# SHEET1.net
KiCad netlist of a schematic drawn in Altium Designer
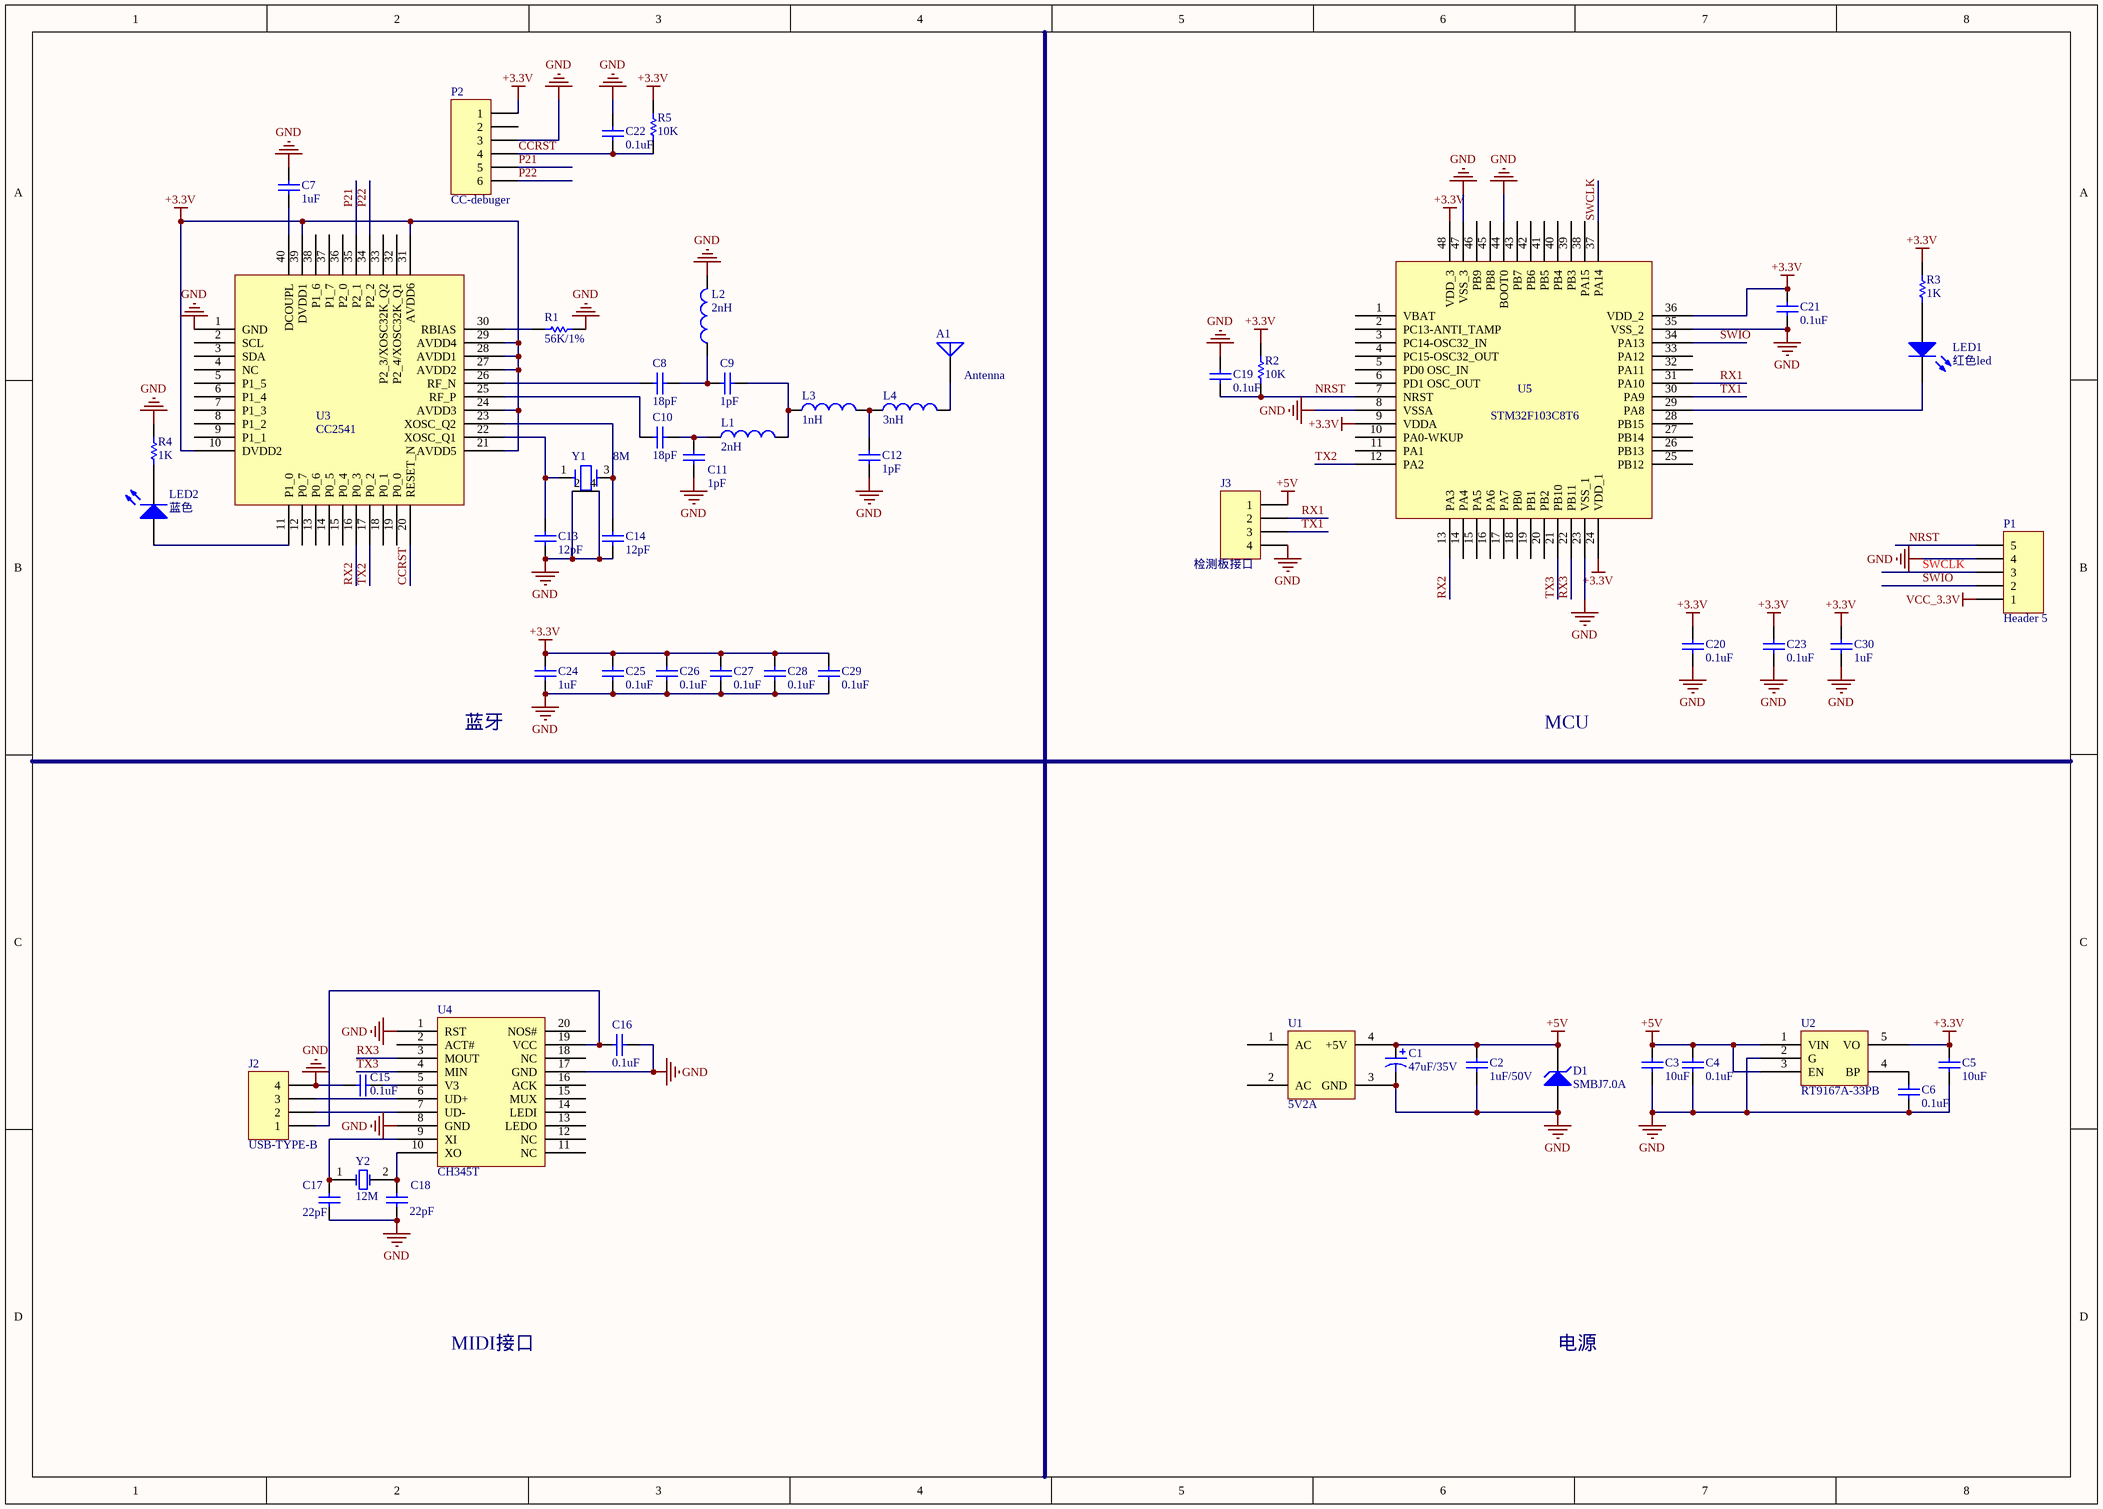
[diagram p0: SHEET1.SCHDOC]

(export (version "E")
  (design (tool "Eeschema 10.0.6"))
  (components
    (comp (ref "A1")
      (value "Antenna")
      (footprint "RF:ANT-PCB-2.4G-IFA-AN043-TI-ORIGIN")
      (description "Generic Antenna")
      (fields (field (name "PUBLISHER") "Altium Limited"))
      (libsource (lib "Miscellaneous Devices") (part "Antenna"))
    )
    (comp (ref "C1")
      (value "47uF/35V")
      (footprint "A")
      (description "Polarized Capacitor (Radial)")
      (fields (field (name "PUBLISHER") "Altium Limited"))
      (libsource (lib "Miscellaneous Devices") (part "Cap Pol1"))
    )
    (comp (ref "C2")
      (value "1uF/50V")
      (footprint "0805")
      (description "Capacitor")
      (fields (field (name "PUBLISHER") "Altium Limited"))
      (libsource (lib "Miscellaneous Devices") (part "Cap"))
    )
    (comp (ref "C3")
      (value "10uF")
      (footprint "0805")
      (description "Capacitor")
      (fields (field (name "PUBLISHER") "Altium Limited"))
      (libsource (lib "Miscellaneous Devices") (part "Cap"))
    )
    (comp (ref "C4")
      (value "0.1uF")
      (description "Capacitor")
      (fields (field (name "PUBLISHER") "Altium Limited"))
      (libsource (lib "Miscellaneous Devices") (part "Cap"))
    )
    (comp (ref "C5")
      (value "10uF")
      (footprint "0805")
      (description "Capacitor")
      (fields (field (name "PUBLISHER") "Altium Limited"))
      (libsource (lib "Miscellaneous Devices") (part "Cap"))
    )
    (comp (ref "C6")
      (value "0.1uF")
      (description "Capacitor")
      (fields (field (name "PUBLISHER") "Altium Limited"))
      (libsource (lib "Miscellaneous Devices") (part "Cap"))
    )
    (comp (ref "C7")
      (value "1uF")
      (description "Capacitor")
      (fields (field (name "PUBLISHER") "Altium Limited"))
      (libsource (lib "Miscellaneous Devices") (part "Cap"))
    )
    (comp (ref "C8")
      (value "18pF")
      (description "Capacitor")
      (fields (field (name "PUBLISHER") "Altium Limited"))
      (libsource (lib "Miscellaneous Devices") (part "Cap"))
    )
    (comp (ref "C9")
      (value "1pF")
      (description "Capacitor")
      (fields (field (name "PUBLISHER") "Altium Limited"))
      (libsource (lib "Miscellaneous Devices") (part "Cap"))
    )
    (comp (ref "C10")
      (value "18pF")
      (description "Capacitor")
      (fields (field (name "PUBLISHER") "Altium Limited"))
      (libsource (lib "Miscellaneous Devices") (part "Cap"))
    )
    (comp (ref "C11")
      (value "1pF")
      (description "Capacitor")
      (fields (field (name "PUBLISHER") "Altium Limited"))
      (libsource (lib "Miscellaneous Devices") (part "Cap"))
    )
    (comp (ref "C12")
      (value "1pF")
      (description "Capacitor")
      (fields (field (name "PUBLISHER") "Altium Limited"))
      (libsource (lib "Miscellaneous Devices") (part "Cap"))
    )
    (comp (ref "C13")
      (value "12pF")
      (description "Capacitor")
      (fields (field (name "PUBLISHER") "Altium Limited"))
      (libsource (lib "Miscellaneous Devices") (part "Cap"))
    )
    (comp (ref "C14")
      (value "12pF")
      (description "Capacitor")
      (fields (field (name "PUBLISHER") "Altium Limited"))
      (libsource (lib "Miscellaneous Devices") (part "Cap"))
    )
    (comp (ref "C15")
      (value "0.1uF")
      (description "Capacitor")
      (fields (field (name "PUBLISHER") "Altium Limited"))
      (libsource (lib "Miscellaneous Devices") (part "Cap"))
    )
    (comp (ref "C16")
      (value "0.1uF")
      (description "Capacitor")
      (fields (field (name "PUBLISHER") "Altium Limited"))
      (libsource (lib "Miscellaneous Devices") (part "Cap"))
    )
    (comp (ref "C17")
      (value "22pF")
      (description "Capacitor")
      (fields (field (name "PUBLISHER") "Altium Limited"))
      (libsource (lib "Miscellaneous Devices") (part "Cap"))
    )
    (comp (ref "C18")
      (value "22pF")
      (description "Capacitor")
      (fields (field (name "PUBLISHER") "Altium Limited"))
      (libsource (lib "Miscellaneous Devices") (part "Cap"))
    )
    (comp (ref "C19")
      (value "0.1uF")
      (description "Capacitor")
      (fields (field (name "PUBLISHER") "Altium Limited"))
      (libsource (lib "Miscellaneous Devices") (part "Cap"))
    )
    (comp (ref "C20")
      (value "0.1uF")
      (description "Capacitor")
      (fields (field (name "PUBLISHER") "Altium Limited"))
      (libsource (lib "Miscellaneous Devices") (part "Cap"))
    )
    (comp (ref "C21")
      (value "0.1uF")
      (description "Capacitor")
      (fields (field (name "PUBLISHER") "Altium Limited"))
      (libsource (lib "Miscellaneous Devices") (part "Cap"))
    )
    (comp (ref "C22")
      (value "0.1uF")
      (description "Capacitor")
      (fields (field (name "PUBLISHER") "Altium Limited"))
      (libsource (lib "Miscellaneous Devices") (part "Cap"))
    )
    (comp (ref "C23")
      (value "0.1uF")
      (description "Capacitor")
      (fields (field (name "PUBLISHER") "Altium Limited"))
      (libsource (lib "Miscellaneous Devices") (part "Cap"))
    )
    (comp (ref "C24")
      (value "1uF")
      (description "Capacitor")
      (fields (field (name "PUBLISHER") "Altium Limited"))
      (libsource (lib "Miscellaneous Devices") (part "Cap"))
    )
    (comp (ref "C25")
      (value "0.1uF")
      (description "Capacitor")
      (fields (field (name "PUBLISHER") "Altium Limited"))
      (libsource (lib "Miscellaneous Devices") (part "Cap"))
    )
    (comp (ref "C26")
      (value "0.1uF")
      (description "Capacitor")
      (fields (field (name "PUBLISHER") "Altium Limited"))
      (libsource (lib "Miscellaneous Devices") (part "Cap"))
    )
    (comp (ref "C27")
      (value "0.1uF")
      (description "Capacitor")
      (fields (field (name "PUBLISHER") "Altium Limited"))
      (libsource (lib "Miscellaneous Devices") (part "Cap"))
    )
    (comp (ref "C28")
      (value "0.1uF")
      (description "Capacitor")
      (fields (field (name "PUBLISHER") "Altium Limited"))
      (libsource (lib "Miscellaneous Devices") (part "Cap"))
    )
    (comp (ref "C29")
      (value "0.1uF")
      (description "Capacitor")
      (fields (field (name "PUBLISHER") "Altium Limited"))
      (libsource (lib "Miscellaneous Devices") (part "Cap"))
    )
    (comp (ref "C30")
      (value "1uF")
      (description "Capacitor")
      (fields (field (name "PUBLISHER") "Altium Limited"))
      (libsource (lib "Miscellaneous Devices") (part "Cap"))
    )
    (comp (ref "D1")
      (value "SMBJ7.0A")
      (footprint "SMD4148")
      (description "Zener Diode")
      (fields (field (name "PUBLISHER") "Altium Limited"))
      (libsource (lib "Miscellaneous Devices") (part "D Zener"))
    )
    (comp (ref "J2")
      (value "USB-TYPE-B")
      (footprint "USB_TYPEB")
      (description "Header, 4-Pin")
      (fields (field (name "PUBLISHER") "Altium Limited"))
      (libsource (lib "") (part "Header 4_1"))
    )
    (comp (ref "J3")
      (value "检测板接口")
      (footprint "USBA")
      (description "Header, 4-Pin")
      (fields (field (name "PUBLISHER") "Altium Limited"))
      (libsource (lib "Miscellaneous Connectors") (part "Header 4"))
    )
    (comp (ref "L1")
      (value "2nH")
      (footprint "0402_SMALL")
      (description "Inductor")
      (fields (field (name "PUBLISHER") "Altium Limited"))
      (libsource (lib "Miscellaneous Devices") (part "Inductor"))
    )
    (comp (ref "L2")
      (value "2nH")
      (footprint "0402_SMALL")
      (description "Inductor")
      (fields (field (name "PUBLISHER") "Altium Limited"))
      (libsource (lib "Miscellaneous Devices") (part "Inductor"))
    )
    (comp (ref "L3")
      (value "1nH")
      (footprint "0402_SMALL")
      (description "Inductor")
      (fields (field (name "PUBLISHER") "Altium Limited"))
      (libsource (lib "Miscellaneous Devices") (part "Inductor"))
    )
    (comp (ref "L4")
      (value "3nH")
      (footprint "0402_SMALL")
      (description "Inductor")
      (fields (field (name "PUBLISHER") "Altium Limited"))
      (libsource (lib "Miscellaneous Devices") (part "Inductor"))
    )
    (comp (ref "LED1")
      (value "红色led")
      (footprint "PIN2")
      (description "Typical INFRARED GaAs LED")
      (fields (field (name "PUBLISHER") "Altium Limited"))
      (libsource (lib "Miscellaneous Devices") (part "LED0"))
    )
    (comp (ref "LED2")
      (value "蓝色")
      (footprint "Miscellaneous Devices:PIN2")
      (description "Typical INFRARED GaAs LED")
      (fields (field (name "PUBLISHER") "Altium Limited"))
      (libsource (lib "Miscellaneous Devices") (part "LED0"))
    )
    (comp (ref "P1")
      (value "Header 5")
      (footprint "5X1.25MMWS")
      (description "Header, 5-Pin")
      (fields (field (name "PUBLISHER") "Altium Limited"))
      (libsource (lib "Miscellaneous Connectors") (part "Header 5"))
    )
    (comp (ref "P2")
      (value "CC-debuger")
      (footprint "MHDR1X6")
      (description "Header, 6-Pin")
      (fields (field (name "PUBLISHER") "Altium Limited"))
      (libsource (lib "Miscellaneous Connectors") (part "Header 6"))
    )
    (comp (ref "R1")
      (value "56K/1%")
      (footprint "0402_SMALL")
      (description "Semiconductor Resistor")
      (fields (field (name "PUBLISHER") "Altium Limited"))
      (libsource (lib "Miscellaneous Devices") (part "Res Semi"))
    )
    (comp (ref "R2")
      (value "10K")
      (footprint "0603")
      (description "Semiconductor Resistor")
      (fields (field (name "PUBLISHER") "Altium Limited"))
      (libsource (lib "Miscellaneous Devices") (part "Res Semi"))
    )
    (comp (ref "R3")
      (value "1K")
      (footprint "0603")
      (description "Semiconductor Resistor")
      (fields (field (name "PUBLISHER") "Altium Limited"))
      (libsource (lib "Miscellaneous Devices") (part "Res Semi"))
    )
    (comp (ref "R4")
      (value "1K")
      (footprint "0402_SMALL")
      (description "Semiconductor Resistor")
      (fields (field (name "PUBLISHER") "Altium Limited"))
      (libsource (lib "Miscellaneous Devices") (part "Res Semi"))
    )
    (comp (ref "R5")
      (value "10K")
      (footprint "0603")
      (description "Semiconductor Resistor")
      (fields (field (name "PUBLISHER") "Altium Limited"))
      (libsource (lib "Miscellaneous Devices") (part "Res Semi"))
    )
    (comp (ref "U1") (value "5V2A") (footprint "PcbLib1:ACDV5V") (libsource (lib "Schlib1") (part "5V2A")))
    (comp (ref "U2")
      (value "RT9167A-33PB")
      (footprint "SOT-23-5")
      (libsource (lib "*") (part "RT9167A-33PB"))
    )
    (comp (ref "U3")
      (value "CC2541")
      (footprint "QFN50P600X600X80-40N")
      (libsource (lib "Schlib1") (part "CC2541"))
    )
    (comp (ref "U4") (value "CH345T") (footprint "SSOP20") (libsource (lib "Schlib1") (part "CH345T")))
    (comp (ref "U5")
      (value "STM32F103C8T6")
      (footprint "LQFP48")
      (libsource (lib "Schlib1") (part "STM32F103C8T6"))
    )
    (comp (ref "Y1")
      (value "8M")
      (footprint "XTAL4TN_3225")
      (libsource (lib "Schlib_20110825") (part "CRYSTAL-4"))
    )
    (comp (ref "Y2")
      (value "12M")
      (footprint "XTAL1")
      (description "Crystal Oscillator")
      (fields (field (name "PUBLISHER") "Altium Limited"))
      (libsource (lib "Miscellaneous Devices") (part "XTAL"))
    )
  )
  (nets
    (net (code "1") (name "+3.3V") (class "Default")
      (node (ref "C20") (pin "1") (pinfunction "1_1") (pintype "passive"))
      (node (ref "C21") (pin "1") (pinfunction "1_1") (pintype "passive"))
      (node (ref "C23") (pin "1") (pinfunction "1_1") (pintype "passive"))
      (node (ref "C24") (pin "1") (pinfunction "1_1") (pintype "passive"))
      (node (ref "C25") (pin "1") (pinfunction "1_1") (pintype "passive"))
      (node (ref "C26") (pin "1") (pinfunction "1_1") (pintype "passive"))
      (node (ref "C27") (pin "1") (pinfunction "1_1") (pintype "passive"))
      (node (ref "C28") (pin "1") (pinfunction "1_1") (pintype "passive"))
      (node (ref "C29") (pin "1") (pinfunction "1_1") (pintype "passive"))
      (node (ref "C30") (pin "1") (pinfunction "1_1") (pintype "passive"))
      (node (ref "C5") (pin "1") (pinfunction "1_1") (pintype "passive"))
      (node (ref "P2") (pin "1") (pinfunction "1_1") (pintype "passive"))
      (node (ref "R2") (pin "2") (pinfunction "2_2") (pintype "passive"))
      (node (ref "R3") (pin "2") (pinfunction "2_2") (pintype "passive"))
      (node (ref "R5") (pin "2") (pinfunction "2_2") (pintype "passive"))
      (node (ref "U2") (pin "5") (pinfunction "VO_5") (pintype "passive"))
      (node (ref "U3") (pin "10") (pinfunction "DVDD2_10") (pintype "passive"))
      (node (ref "U3") (pin "21") (pinfunction "AVDD5_21") (pintype "passive"))
      (node (ref "U3") (pin "24") (pinfunction "AVDD3_24") (pintype "passive"))
      (node (ref "U3") (pin "27") (pinfunction "AVDD2_27") (pintype "passive"))
      (node (ref "U3") (pin "28") (pinfunction "AVDD1_28") (pintype "passive"))
      (node (ref "U3") (pin "29") (pinfunction "AVDD4_29") (pintype "passive"))
      (node (ref "U3") (pin "31") (pinfunction "AVDD6_31") (pintype "passive"))
      (node (ref "U3") (pin "39") (pinfunction "DVDD1_39") (pintype "passive"))
      (node (ref "U5") (pin "24") (pinfunction "VDD_1_24") (pintype "passive"))
      (node (ref "U5") (pin "36") (pinfunction "VDD_2_36") (pintype "passive"))
      (node (ref "U5") (pin "48") (pinfunction "VDD_3_48") (pintype "passive"))
      (node (ref "U5") (pin "9") (pinfunction "VDDA_9") (pintype "passive"))
    )
    (net (code "2") (name "+5V") (class "Default")
      (node (ref "C1") (pin "1") (pinfunction "1_1") (pintype "passive"))
      (node (ref "C2") (pin "1") (pinfunction "1_1") (pintype "passive"))
      (node (ref "C3") (pin "1") (pinfunction "1_1") (pintype "passive"))
      (node (ref "C4") (pin "2") (pinfunction "2_2") (pintype "passive"))
      (node (ref "D1") (pin "2") (pinfunction "K_2") (pintype "passive"))
      (node (ref "J3") (pin "1") (pinfunction "1_1") (pintype "passive"))
      (node (ref "U1") (pin "4") (pinfunction "+5V_4") (pintype "passive"))
      (node (ref "U2") (pin "1") (pinfunction "VIN_1") (pintype "passive"))
      (node (ref "U2") (pin "3") (pinfunction "EN_3") (pintype "passive"))
    )
    (net (code "3") (name "/CCRST") (class "Default")
      (node (ref "C22") (pin "2") (pinfunction "2_2") (pintype "passive"))
      (node (ref "P2") (pin "4") (pinfunction "4_4") (pintype "passive"))
      (node (ref "R5") (pin "1") (pinfunction "1_1") (pintype "passive"))
      (node (ref "U3") (pin "20") (pinfunction "RESET_N_20") (pintype "passive"))
    )
    (net (code "4") (name "/NRST") (class "Default")
      (node (ref "C19") (pin "2") (pinfunction "2_2") (pintype "passive"))
      (node (ref "P1") (pin "5") (pinfunction "5_5") (pintype "passive"))
      (node (ref "R2") (pin "1") (pinfunction "1_1") (pintype "passive"))
      (node (ref "U5") (pin "7") (pinfunction "NRST_7") (pintype "passive"))
    )
    (net (code "5") (name "/P21") (class "Default")
      (node (ref "P2") (pin "5") (pinfunction "5_5") (pintype "passive"))
      (node (ref "U3") (pin "35") (pinfunction "P2_1_35") (pintype "passive"))
    )
    (net (code "6") (name "/P22") (class "Default")
      (node (ref "P2") (pin "6") (pinfunction "6_6") (pintype "passive"))
      (node (ref "U3") (pin "34") (pinfunction "P2_2_34") (pintype "passive"))
    )
    (net (code "7") (name "/RX1") (class "Default")
      (node (ref "J3") (pin "2") (pinfunction "2_2") (pintype "passive"))
      (node (ref "U5") (pin "31") (pinfunction "PA10_31") (pintype "passive"))
    )
    (net (code "8") (name "/RX2") (class "Default")
      (node (ref "U3") (pin "16") (pinfunction "P0_3_16") (pintype "passive"))
      (node (ref "U5") (pin "13") (pinfunction "PA3_13") (pintype "passive"))
    )
    (net (code "9") (name "/RX3") (class "Default")
      (node (ref "U4") (pin "3") (pinfunction "MOUT_3") (pintype "passive"))
      (node (ref "U5") (pin "22") (pinfunction "PB11_22") (pintype "passive"))
    )
    (net (code "10") (name "/SWCLK") (class "Default")
      (node (ref "P1") (pin "3") (pinfunction "3_3") (pintype "passive"))
      (node (ref "U5") (pin "37") (pinfunction "PA14_37") (pintype "passive"))
    )
    (net (code "11") (name "/SWIO") (class "Default")
      (node (ref "P1") (pin "2") (pinfunction "2_2") (pintype "passive"))
      (node (ref "U5") (pin "34") (pinfunction "PA13_34") (pintype "passive"))
    )
    (net (code "12") (name "/TX1") (class "Default")
      (node (ref "J3") (pin "3") (pinfunction "3_3") (pintype "passive"))
      (node (ref "U5") (pin "30") (pinfunction "PA9_30") (pintype "passive"))
    )
    (net (code "13") (name "/TX2") (class "Default")
      (node (ref "U3") (pin "17") (pinfunction "P0_2_17") (pintype "passive"))
      (node (ref "U5") (pin "12") (pinfunction "PA2_12") (pintype "passive"))
    )
    (net (code "14") (name "/TX3") (class "Default")
      (node (ref "U4") (pin "4") (pinfunction "MIN_4") (pintype "passive"))
      (node (ref "U5") (pin "21") (pinfunction "PB10_21") (pintype "passive"))
    )
    (net (code "15") (name "GND") (class "Default")
      (node (ref "C1") (pin "2") (pinfunction "2_2") (pintype "passive"))
      (node (ref "C11") (pin "1") (pinfunction "1_1") (pintype "passive"))
      (node (ref "C12") (pin "1") (pinfunction "1_1") (pintype "passive"))
      (node (ref "C13") (pin "2") (pinfunction "2_2") (pintype "passive"))
      (node (ref "C14") (pin "2") (pinfunction "2_2") (pintype "passive"))
      (node (ref "C15") (pin "2") (pinfunction "2_2") (pintype "passive"))
      (node (ref "C16") (pin "1") (pinfunction "1_1") (pintype "passive"))
      (node (ref "C17") (pin "2") (pinfunction "2_2") (pintype "passive"))
      (node (ref "C18") (pin "2") (pinfunction "2_2") (pintype "passive"))
      (node (ref "C19") (pin "1") (pinfunction "1_1") (pintype "passive"))
      (node (ref "C2") (pin "2") (pinfunction "2_2") (pintype "passive"))
      (node (ref "C20") (pin "2") (pinfunction "2_2") (pintype "passive"))
      (node (ref "C21") (pin "2") (pinfunction "2_2") (pintype "passive"))
      (node (ref "C22") (pin "1") (pinfunction "1_1") (pintype "passive"))
      (node (ref "C23") (pin "2") (pinfunction "2_2") (pintype "passive"))
      (node (ref "C24") (pin "2") (pinfunction "2_2") (pintype "passive"))
      (node (ref "C25") (pin "2") (pinfunction "2_2") (pintype "passive"))
      (node (ref "C26") (pin "2") (pinfunction "2_2") (pintype "passive"))
      (node (ref "C27") (pin "2") (pinfunction "2_2") (pintype "passive"))
      (node (ref "C28") (pin "2") (pinfunction "2_2") (pintype "passive"))
      (node (ref "C29") (pin "2") (pinfunction "2_2") (pintype "passive"))
      (node (ref "C3") (pin "2") (pinfunction "2_2") (pintype "passive"))
      (node (ref "C30") (pin "2") (pinfunction "2_2") (pintype "passive"))
      (node (ref "C4") (pin "1") (pinfunction "1_1") (pintype "passive"))
      (node (ref "C5") (pin "2") (pinfunction "2_2") (pintype "passive"))
      (node (ref "C6") (pin "1") (pinfunction "1_1") (pintype "passive"))
      (node (ref "C7") (pin "2") (pinfunction "2_2") (pintype "passive"))
      (node (ref "D1") (pin "1") (pinfunction "A_1") (pintype "passive"))
      (node (ref "J2") (pin "4") (pinfunction "4_4") (pintype "passive"))
      (node (ref "J3") (pin "4") (pinfunction "4_4") (pintype "passive"))
      (node (ref "L2") (pin "2") (pinfunction "2_2") (pintype "passive"))
      (node (ref "P1") (pin "4") (pinfunction "4_4") (pintype "passive"))
      (node (ref "P2") (pin "3") (pinfunction "3_3") (pintype "passive"))
      (node (ref "R1") (pin "2") (pinfunction "2_2") (pintype "passive"))
      (node (ref "R4") (pin "1") (pinfunction "1_1") (pintype "passive"))
      (node (ref "U1") (pin "3") (pinfunction "GND_3") (pintype "passive"))
      (node (ref "U2") (pin "2") (pinfunction "G_2") (pintype "passive"))
      (node (ref "U3") (pin "1") (pinfunction "GND_1") (pintype "passive"))
      (node (ref "U4") (pin "1") (pinfunction "RST_1") (pintype "passive"))
      (node (ref "U4") (pin "17") (pinfunction "GND_17") (pintype "passive"))
      (node (ref "U4") (pin "8") (pinfunction "GND_8") (pintype "passive"))
      (node (ref "U5") (pin "23") (pinfunction "VSS_1_23") (pintype "passive"))
      (node (ref "U5") (pin "35") (pinfunction "VSS_2_35") (pintype "passive"))
      (node (ref "U5") (pin "44") (pinfunction "BOOT0_44") (pintype "passive"))
      (node (ref "U5") (pin "47") (pinfunction "VSS_3_47") (pintype "passive"))
      (node (ref "U5") (pin "8") (pinfunction "VSSA_8") (pintype "passive"))
      (node (ref "Y1") (pin "2") (pinfunction "GND_2") (pintype "passive"))
      (node (ref "Y1") (pin "4") (pinfunction "GND_4") (pintype "passive"))
    )
    (net (code "16") (name "Net-(A1-A)") (class "Default")
      (node (ref "A1") (pin "1") (pinfunction "A_1") (pintype "passive"))
      (node (ref "L4") (pin "2") (pinfunction "2_2") (pintype "passive"))
    )
    (net (code "17") (name "Net-(C8-Pad1)") (class "Default")
      (node (ref "C8") (pin "1") (pinfunction "1_1") (pintype "passive"))
      (node (ref "C9") (pin "2") (pinfunction "2_2") (pintype "passive"))
      (node (ref "L2") (pin "1") (pinfunction "1_1") (pintype "passive"))
    )
    (net (code "18") (name "Net-(C9-Pad1)") (class "Default")
      (node (ref "C9") (pin "1") (pinfunction "1_1") (pintype "passive"))
      (node (ref "L1") (pin "2") (pinfunction "2_2") (pintype "passive"))
      (node (ref "L3") (pin "1") (pinfunction "1_1") (pintype "passive"))
    )
    (net (code "19") (name "Net-(C10-Pad1)") (class "Default")
      (node (ref "C10") (pin "1") (pinfunction "1_1") (pintype "passive"))
      (node (ref "C11") (pin "2") (pinfunction "2_2") (pintype "passive"))
      (node (ref "L1") (pin "1") (pinfunction "1_1") (pintype "passive"))
    )
    (net (code "20") (name "Net-(C12-Pad2)") (class "Default")
      (node (ref "C12") (pin "2") (pinfunction "2_2") (pintype "passive"))
      (node (ref "L3") (pin "2") (pinfunction "2_2") (pintype "passive"))
      (node (ref "L4") (pin "1") (pinfunction "1_1") (pintype "passive"))
    )
    (net (code "21") (name "Net-(LED1-A)") (class "Default")
      (node (ref "LED1") (pin "1") (pinfunction "A_1") (pintype "passive"))
      (node (ref "R3") (pin "1") (pinfunction "1_1") (pintype "passive"))
    )
    (net (code "22") (name "Net-(LED1-K)") (class "Default")
      (node (ref "LED1") (pin "2") (pinfunction "K_2") (pintype "passive"))
      (node (ref "U5") (pin "29") (pinfunction "PA8_29") (pintype "passive"))
    )
    (net (code "23") (name "Net-(LED2-A)") (class "Default")
      (node (ref "LED2") (pin "1") (pinfunction "A_1") (pintype "passive"))
      (node (ref "U3") (pin "11") (pinfunction "P1_0_11") (pintype "passive"))
    )
    (net (code "24") (name "Net-(LED2-K)") (class "Default")
      (node (ref "LED2") (pin "2") (pinfunction "K_2") (pintype "passive"))
      (node (ref "R4") (pin "2") (pinfunction "2_2") (pintype "passive"))
    )
    (net (code "25") (name "Net-(U2-BP)") (class "Default")
      (node (ref "C6") (pin "2") (pinfunction "2_2") (pintype "passive"))
      (node (ref "U2") (pin "4") (pinfunction "BP_4") (pintype "passive"))
    )
    (net (code "26") (name "Net-(U3-DCOUPL)") (class "Default")
      (node (ref "C7") (pin "1") (pinfunction "1_1") (pintype "passive"))
      (node (ref "U3") (pin "40") (pinfunction "DCOUPL_40") (pintype "passive"))
    )
    (net (code "27") (name "Net-(U3-RBIAS)") (class "Default")
      (node (ref "R1") (pin "1") (pinfunction "1_1") (pintype "passive"))
      (node (ref "U3") (pin "30") (pinfunction "RBIAS_30") (pintype "passive"))
    )
    (net (code "28") (name "Net-(U3-RF_N)") (class "Default")
      (node (ref "C8") (pin "2") (pinfunction "2_2") (pintype "passive"))
      (node (ref "U3") (pin "26") (pinfunction "RF_N_26") (pintype "passive"))
    )
    (net (code "29") (name "Net-(U3-RF_P)") (class "Default")
      (node (ref "C10") (pin "2") (pinfunction "2_2") (pintype "passive"))
      (node (ref "U3") (pin "25") (pinfunction "RF_P_25") (pintype "passive"))
    )
    (net (code "30") (name "Net-(U3-XOSC_Q1)") (class "Default")
      (node (ref "C13") (pin "1") (pinfunction "1_1") (pintype "passive"))
      (node (ref "U3") (pin "22") (pinfunction "XOSC_Q1_22") (pintype "passive"))
      (node (ref "Y1") (pin "1") (pinfunction "X1_1") (pintype "passive"))
    )
    (net (code "31") (name "Net-(U3-XOSC_Q2)") (class "Default")
      (node (ref "C14") (pin "1") (pinfunction "1_1") (pintype "passive"))
      (node (ref "U3") (pin "23") (pinfunction "XOSC_Q2_23") (pintype "passive"))
      (node (ref "Y1") (pin "3") (pinfunction "X2_3") (pintype "passive"))
    )
    (net (code "32") (name "Net-(U4-UD+)") (class "Default")
      (node (ref "J2") (pin "3") (pinfunction "3_3") (pintype "passive"))
      (node (ref "U4") (pin "6") (pinfunction "UD+_6") (pintype "passive"))
    )
    (net (code "33") (name "Net-(U4-UD-)") (class "Default")
      (node (ref "J2") (pin "2") (pinfunction "2_2") (pintype "passive"))
      (node (ref "U4") (pin "7") (pinfunction "UD-_7") (pintype "passive"))
    )
    (net (code "34") (name "Net-(U4-V3)") (class "Default")
      (node (ref "C15") (pin "1") (pinfunction "1_1") (pintype "passive"))
      (node (ref "U4") (pin "5") (pinfunction "V3_5") (pintype "passive"))
    )
    (net (code "35") (name "Net-(U4-VCC)") (class "Default")
      (node (ref "C16") (pin "2") (pinfunction "2_2") (pintype "passive"))
      (node (ref "J2") (pin "1") (pinfunction "1_1") (pintype "passive"))
      (node (ref "U4") (pin "19") (pinfunction "VCC_19") (pintype "passive"))
    )
    (net (code "36") (name "Net-(U4-XI)") (class "Default")
      (node (ref "C17") (pin "1") (pinfunction "1_1") (pintype "passive"))
      (node (ref "U4") (pin "9") (pinfunction "XI_9") (pintype "passive"))
      (node (ref "Y2") (pin "1") (pinfunction "OSC1_1") (pintype "passive"))
    )
    (net (code "37") (name "Net-(U4-XO)") (class "Default")
      (node (ref "C18") (pin "1") (pinfunction "1_1") (pintype "passive"))
      (node (ref "U4") (pin "10") (pinfunction "XO_10") (pintype "passive"))
      (node (ref "Y2") (pin "2") (pinfunction "OSC2_2") (pintype "passive"))
    )
    (net (code "38") (name "VCC_3.3V") (class "Default")
      (node (ref "P1") (pin "1") (pinfunction "1_1") (pintype "passive"))
    )
    (net (code "39") (name "unconnected-(P2-Pad2)") (class "Default")
      (node (ref "P2") (pin "2") (pinfunction "2_2") (pintype "passive"))
    )
    (net (code "40") (name "unconnected-(U1-AC-Pad1)") (class "Default")
      (node (ref "U1") (pin "1") (pinfunction "AC_1") (pintype "passive"))
    )
    (net (code "41") (name "unconnected-(U1-AC-Pad2)") (class "Default")
      (node (ref "U1") (pin "2") (pinfunction "AC_2") (pintype "passive"))
    )
    (net (code "42") (name "unconnected-(U3-NC-Pad4)") (class "Default")
      (node (ref "U3") (pin "4") (pinfunction "NC_4") (pintype "passive"))
    )
    (net (code "43") (name "unconnected-(U3-P0_0-Pad19)") (class "Default")
      (node (ref "U3") (pin "19") (pinfunction "P0_0_19") (pintype "passive"))
    )
    (net (code "44") (name "unconnected-(U3-P0_1-Pad18)") (class "Default")
      (node (ref "U3") (pin "18") (pinfunction "P0_1_18") (pintype "passive"))
    )
    (net (code "45") (name "unconnected-(U3-P0_4-Pad15)") (class "Default")
      (node (ref "U3") (pin "15") (pinfunction "P0_4_15") (pintype "passive"))
    )
    (net (code "46") (name "unconnected-(U3-P0_5-Pad14)") (class "Default")
      (node (ref "U3") (pin "14") (pinfunction "P0_5_14") (pintype "passive"))
    )
    (net (code "47") (name "unconnected-(U3-P0_6-Pad13)") (class "Default")
      (node (ref "U3") (pin "13") (pinfunction "P0_6_13") (pintype "passive"))
    )
    (net (code "48") (name "unconnected-(U3-P0_7-Pad12)") (class "Default")
      (node (ref "U3") (pin "12") (pinfunction "P0_7_12") (pintype "passive"))
    )
    (net (code "49") (name "unconnected-(U3-P1_1-Pad9)") (class "Default")
      (node (ref "U3") (pin "9") (pinfunction "P1_1_9") (pintype "passive"))
    )
    (net (code "50") (name "unconnected-(U3-P1_2-Pad8)") (class "Default")
      (node (ref "U3") (pin "8") (pinfunction "P1_2_8") (pintype "passive"))
    )
    (net (code "51") (name "unconnected-(U3-P1_3-Pad7)") (class "Default")
      (node (ref "U3") (pin "7") (pinfunction "P1_3_7") (pintype "passive"))
    )
    (net (code "52") (name "unconnected-(U3-P1_4-Pad6)") (class "Default")
      (node (ref "U3") (pin "6") (pinfunction "P1_4_6") (pintype "passive"))
    )
    (net (code "53") (name "unconnected-(U3-P1_5-Pad5)") (class "Default")
      (node (ref "U3") (pin "5") (pinfunction "P1_5_5") (pintype "passive"))
    )
    (net (code "54") (name "unconnected-(U3-P1_6-Pad38)") (class "Default")
      (node (ref "U3") (pin "38") (pinfunction "P1_6_38") (pintype "passive"))
    )
    (net (code "55") (name "unconnected-(U3-P1_7-Pad37)") (class "Default")
      (node (ref "U3") (pin "37") (pinfunction "P1_7_37") (pintype "passive"))
    )
    (net (code "56") (name "unconnected-(U3-P2_0-Pad36)") (class "Default")
      (node (ref "U3") (pin "36") (pinfunction "P2_0_36") (pintype "passive"))
    )
    (net (code "57") (name "unconnected-(U3-P2_3{slash}XOSC32K_Q2-Pad33)") (class "Default")
      (node (ref "U3") (pin "33") (pinfunction "P2_3/XOSC32K_Q2_33") (pintype "passive"))
    )
    (net (code "58") (name "unconnected-(U3-P2_4{slash}XOSC32K_Q1-Pad32)") (class "Default")
      (node (ref "U3") (pin "32") (pinfunction "P2_4/XOSC32K_Q1_32") (pintype "passive"))
    )
    (net (code "59") (name "unconnected-(U3-SCL-Pad2)") (class "Default")
      (node (ref "U3") (pin "2") (pinfunction "SCL_2") (pintype "passive"))
    )
    (net (code "60") (name "unconnected-(U3-SDA-Pad3)") (class "Default")
      (node (ref "U3") (pin "3") (pinfunction "SDA_3") (pintype "passive"))
    )
    (net (code "61") (name "unconnected-(U4-ACK-Pad16)") (class "Default")
      (node (ref "U4") (pin "16") (pinfunction "ACK_16") (pintype "passive"))
    )
    (net (code "62") (name "unconnected-(U4-ACT#-Pad2)") (class "Default")
      (node (ref "U4") (pin "2") (pinfunction "ACT#_2") (pintype "passive"))
    )
    (net (code "63") (name "unconnected-(U4-LEDI-Pad14)") (class "Default")
      (node (ref "U4") (pin "14") (pinfunction "LEDI_14") (pintype "passive"))
    )
    (net (code "64") (name "unconnected-(U4-LEDO-Pad13)") (class "Default")
      (node (ref "U4") (pin "13") (pinfunction "LEDO_13") (pintype "passive"))
    )
    (net (code "65") (name "unconnected-(U4-MUX-Pad15)") (class "Default")
      (node (ref "U4") (pin "15") (pinfunction "MUX_15") (pintype "passive"))
    )
    (net (code "66") (name "unconnected-(U4-NC-Pad11)") (class "Default")
      (node (ref "U4") (pin "11") (pinfunction "NC_11") (pintype "passive"))
    )
    (net (code "67") (name "unconnected-(U4-NC-Pad12)") (class "Default")
      (node (ref "U4") (pin "12") (pinfunction "NC_12") (pintype "passive"))
    )
    (net (code "68") (name "unconnected-(U4-NC-Pad18)") (class "Default")
      (node (ref "U4") (pin "18") (pinfunction "NC_18") (pintype "passive"))
    )
    (net (code "69") (name "unconnected-(U4-NOS#-Pad20)") (class "Default")
      (node (ref "U4") (pin "20") (pinfunction "NOS#_20") (pintype "passive"))
    )
    (net (code "70") (name "unconnected-(U5-PA0-WKUP-Pad10)") (class "Default")
      (node (ref "U5") (pin "10") (pinfunction "PA0-WKUP_10") (pintype "passive"))
    )
    (net (code "71") (name "unconnected-(U5-PA1-Pad11)") (class "Default")
      (node (ref "U5") (pin "11") (pinfunction "PA1_11") (pintype "passive"))
    )
    (net (code "72") (name "unconnected-(U5-PA4-Pad14)") (class "Default")
      (node (ref "U5") (pin "14") (pinfunction "PA4_14") (pintype "passive"))
    )
    (net (code "73") (name "unconnected-(U5-PA5-Pad15)") (class "Default")
      (node (ref "U5") (pin "15") (pinfunction "PA5_15") (pintype "passive"))
    )
    (net (code "74") (name "unconnected-(U5-PA6-Pad16)") (class "Default")
      (node (ref "U5") (pin "16") (pinfunction "PA6_16") (pintype "passive"))
    )
    (net (code "75") (name "unconnected-(U5-PA7-Pad17)") (class "Default")
      (node (ref "U5") (pin "17") (pinfunction "PA7_17") (pintype "passive"))
    )
    (net (code "76") (name "unconnected-(U5-PA11-Pad32)") (class "Default")
      (node (ref "U5") (pin "32") (pinfunction "PA11_32") (pintype "passive"))
    )
    (net (code "77") (name "unconnected-(U5-PA12-Pad33)") (class "Default")
      (node (ref "U5") (pin "33") (pinfunction "PA12_33") (pintype "passive"))
    )
    (net (code "78") (name "unconnected-(U5-PA15-Pad38)") (class "Default")
      (node (ref "U5") (pin "38") (pinfunction "PA15_38") (pintype "passive"))
    )
    (net (code "79") (name "unconnected-(U5-PB0-Pad18)") (class "Default")
      (node (ref "U5") (pin "18") (pinfunction "PB0_18") (pintype "passive"))
    )
    (net (code "80") (name "unconnected-(U5-PB1-Pad19)") (class "Default")
      (node (ref "U5") (pin "19") (pinfunction "PB1_19") (pintype "passive"))
    )
    (net (code "81") (name "unconnected-(U5-PB2-Pad20)") (class "Default")
      (node (ref "U5") (pin "20") (pinfunction "PB2_20") (pintype "passive"))
    )
    (net (code "82") (name "unconnected-(U5-PB3-Pad39)") (class "Default")
      (node (ref "U5") (pin "39") (pinfunction "PB3_39") (pintype "passive"))
    )
    (net (code "83") (name "unconnected-(U5-PB4-Pad40)") (class "Default")
      (node (ref "U5") (pin "40") (pinfunction "PB4_40") (pintype "passive"))
    )
    (net (code "84") (name "unconnected-(U5-PB5-Pad41)") (class "Default")
      (node (ref "U5") (pin "41") (pinfunction "PB5_41") (pintype "passive"))
    )
    (net (code "85") (name "unconnected-(U5-PB6-Pad42)") (class "Default")
      (node (ref "U5") (pin "42") (pinfunction "PB6_42") (pintype "passive"))
    )
    (net (code "86") (name "unconnected-(U5-PB7-Pad43)") (class "Default")
      (node (ref "U5") (pin "43") (pinfunction "PB7_43") (pintype "passive"))
    )
    (net (code "87") (name "unconnected-(U5-PB8-Pad45)") (class "Default")
      (node (ref "U5") (pin "45") (pinfunction "PB8_45") (pintype "passive"))
    )
    (net (code "88") (name "unconnected-(U5-PB9-Pad46)") (class "Default")
      (node (ref "U5") (pin "46") (pinfunction "PB9_46") (pintype "passive"))
    )
    (net (code "89") (name "unconnected-(U5-PB12-Pad25)") (class "Default")
      (node (ref "U5") (pin "25") (pinfunction "PB12_25") (pintype "passive"))
    )
    (net (code "90") (name "unconnected-(U5-PB13-Pad26)") (class "Default")
      (node (ref "U5") (pin "26") (pinfunction "PB13_26") (pintype "passive"))
    )
    (net (code "91") (name "unconnected-(U5-PB14-Pad27)") (class "Default")
      (node (ref "U5") (pin "27") (pinfunction "PB14_27") (pintype "passive"))
    )
    (net (code "92") (name "unconnected-(U5-PB15-Pad28)") (class "Default")
      (node (ref "U5") (pin "28") (pinfunction "PB15_28") (pintype "passive"))
    )
    (net (code "93") (name "unconnected-(U5-PC13-ANTI_TAMP-Pad2)") (class "Default")
      (node (ref "U5") (pin "2") (pinfunction "PC13-ANTI_TAMP_2") (pintype "passive"))
    )
    (net (code "94") (name "unconnected-(U5-PC14-OSC32_IN-Pad3)") (class "Default")
      (node (ref "U5") (pin "3") (pinfunction "PC14-OSC32_IN_3") (pintype "passive"))
    )
    (net (code "95") (name "unconnected-(U5-PC15-OSC32_OUT-Pad4)") (class "Default")
      (node (ref "U5") (pin "4") (pinfunction "PC15-OSC32_OUT_4") (pintype "passive"))
    )
    (net (code "96") (name "unconnected-(U5-PD0_OSC_IN-Pad5)") (class "Default")
      (node (ref "U5") (pin "5") (pinfunction "PD0_OSC_IN_5") (pintype "passive"))
    )
    (net (code "97") (name "unconnected-(U5-PD1_OSC_OUT-Pad6)") (class "Default")
      (node (ref "U5") (pin "6") (pinfunction "PD1_OSC_OUT_6") (pintype "passive"))
    )
    (net (code "98") (name "unconnected-(U5-VBAT-Pad1)") (class "Default")
      (node (ref "U5") (pin "1") (pinfunction "VBAT_1") (pintype "passive"))
    )
  )
)
